# ProProject_PetCareSTM32_MiniSTM32_2024-0.net
KiCad netlist of a schematic drawn in EasyEDA Pro
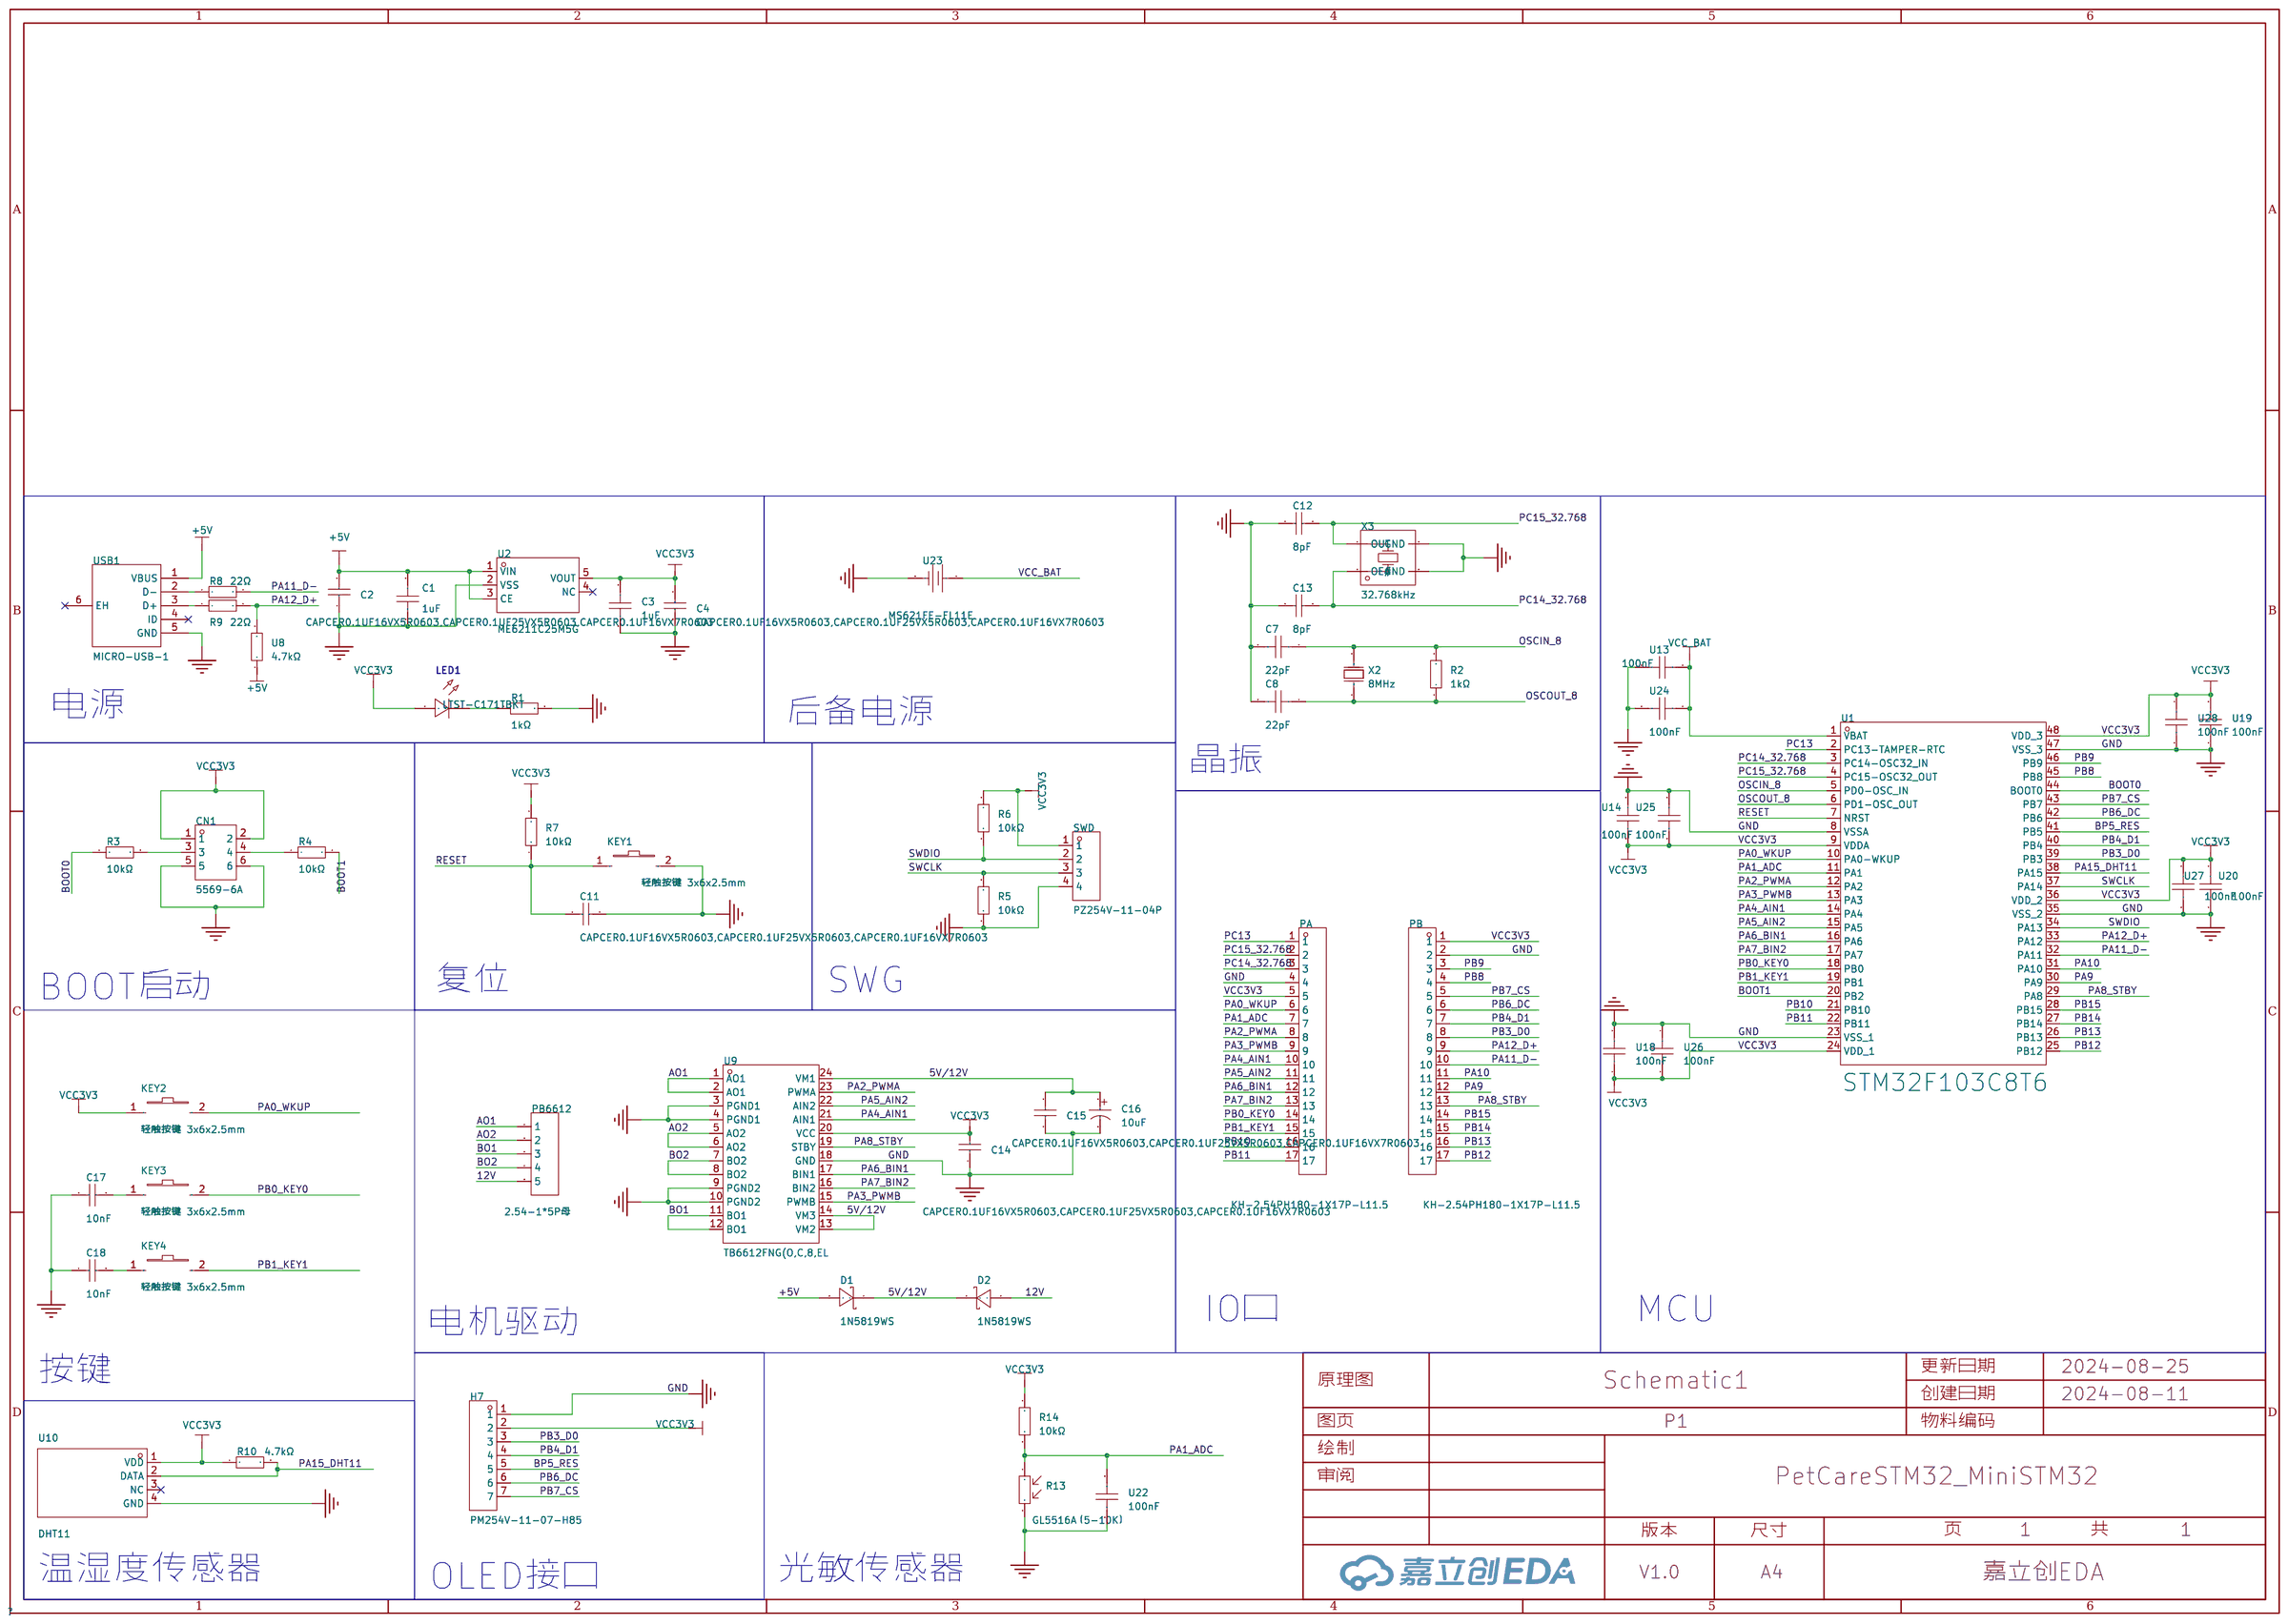
[diagram p0: schematic sheet]

(export (version "E")
  (design (tool "Eeschema 10.0.6"))
  (components
    (comp (ref "C1")
      (value "1uF")
      (footprint "easyedapro:C0603")
      (description "容值:1uF;精度:±10%;额定电压:50V;材质(温度系数):X5R;")
      (fields
        (field (name "Manufacturer Part") "CL10A105KB8NNNC")
        (field (name "Manufacturer") "SAMSUNG(三星)")
      )
      (libsource (lib "easyedapro") (part "CL10A105KB8NNNC"))
    )
    (comp (ref "C2")
      (value "CAPCER0.1UF16VX5R0603,CAPCER0.1UF25VX5R0603,CAPCER0.1UF16VX7R0603")
      (footprint "easyedapro:C0603")
      (libsource (lib "easyedapro") (part "CAPCER0.1UF16VX5R0603,CAPCER0.1UF25VX5R0603,CAPCER0.1UF16VX7R0603"))
    )
    (comp (ref "C3")
      (value "1uF")
      (footprint "easyedapro:C0603")
      (description "容值:1uF;精度:±10%;额定电压:50V;材质(温度系数):X5R;")
      (fields
        (field (name "Manufacturer Part") "CL10A105KB8NNNC")
        (field (name "Manufacturer") "SAMSUNG(三星)")
      )
      (libsource (lib "easyedapro") (part "CL10A105KB8NNNC"))
    )
    (comp (ref "C4")
      (value "CAPCER0.1UF16VX5R0603,CAPCER0.1UF25VX5R0603,CAPCER0.1UF16VX7R0603")
      (footprint "easyedapro:C0603")
      (libsource (lib "easyedapro") (part "CAPCER0.1UF16VX5R0603,CAPCER0.1UF25VX5R0603,CAPCER0.1UF16VX7R0603"))
    )
    (comp (ref "C7")
      (value "22pF")
      (footprint "easyedapro:C0603")
      (description "容值:22pF;精度:±5%;额定电压:50V;材质(温度系数):C0G;")
      (fields
        (field (name "Manufacturer Part") "CL10C220JB81PNC")
        (field (name "Manufacturer") "SAMSUNG(三星)")
      )
      (libsource (lib "easyedapro") (part "CL10C220JB81PNC"))
    )
    (comp (ref "C8")
      (value "22pF")
      (footprint "easyedapro:C0603")
      (description "容值:22pF;精度:±5%;额定电压:50V;材质(温度系数):C0G;")
      (fields
        (field (name "Manufacturer Part") "CL10C220JB81PNC")
        (field (name "Manufacturer") "SAMSUNG(三星)")
      )
      (libsource (lib "easyedapro") (part "CL10C220JB81PNC"))
    )
    (comp (ref "C11")
      (value "CAPCER0.1UF16VX5R0603,CAPCER0.1UF25VX5R0603,CAPCER0.1UF16VX7R0603")
      (footprint "easyedapro:C0603")
      (libsource (lib "easyedapro") (part "CAPCER0.1UF16VX5R0603,CAPCER0.1UF25VX5R0603,CAPCER0.1UF16VX7R0603"))
    )
    (comp (ref "C12")
      (value "8pF")
      (footprint "easyedapro:C0603")
      (description "容值:8pF;额定电压:50V;材质(温度系数):C0G;")
      (fields (field (name "Manufacturer Part") "0603CG8R0C500NT") (field (name "Manufacturer") "FH(风华)"))
      (libsource (lib "easyedapro") (part "0603CG8R0C500NT_C36508"))
    )
    (comp (ref "C13")
      (value "8pF")
      (footprint "easyedapro:C0603")
      (description "容值:8pF;额定电压:50V;材质(温度系数):C0G;")
      (fields (field (name "Manufacturer Part") "0603CG8R0C500NT") (field (name "Manufacturer") "FH(风华)"))
      (libsource (lib "easyedapro") (part "0603CG8R0C500NT_C36508"))
    )
    (comp (ref "C14")
      (value "CAPCER0.1UF16VX5R0603,CAPCER0.1UF25VX5R0603,CAPCER0.1UF16VX7R0603")
      (footprint "easyedapro:C0603")
      (libsource (lib "easyedapro") (part "CAPCER0.1UF16VX5R0603,CAPCER0.1UF25VX5R0603,CAPCER0.1UF16VX7R0603"))
    )
    (comp (ref "C15")
      (value "CAPCER0.1UF16VX5R0603,CAPCER0.1UF25VX5R0603,CAPCER0.1UF16VX7R0603")
      (footprint "easyedapro:C0603")
      (libsource (lib "easyedapro") (part "CAPCER0.1UF16VX5R0603,CAPCER0.1UF25VX5R0603,CAPCER0.1UF16VX7R0603"))
    )
    (comp (ref "C16")
      (value "10uF")
      (footprint "easyedapro:CAP-TH_BD5.0-P2.00-D0.8-FD")
      (description "容值:10uF;精度:±20%;额定电压:25V;")
      (fields (field (name "Manufacturer Part") "KF100M025C110A") (field (name "Manufacturer") "CapXon(丰宾)"))
      (libsource (lib "easyedapro") (part "KF100M025C110A"))
    )
    (comp (ref "C17")
      (value "10nF")
      (footprint "easyedapro:C0603")
      (description "容值:10nF;精度:±10%;额定电压:50V;材质(温度系数):X7R;")
      (fields
        (field (name "Manufacturer Part") "CC0603KRX7R9BB103")
        (field (name "Manufacturer") "YAGEO(国巨)")
      )
      (libsource (lib "easyedapro") (part "CC0603KRX7R9BB103"))
    )
    (comp (ref "C18")
      (value "10nF")
      (footprint "easyedapro:C0603")
      (description "容值:10nF;精度:±10%;额定电压:50V;材质(温度系数):X7R;")
      (fields
        (field (name "Manufacturer Part") "CC0603KRX7R9BB103")
        (field (name "Manufacturer") "YAGEO(国巨)")
      )
      (libsource (lib "easyedapro") (part "CC0603KRX7R9BB103"))
    )
    (comp (ref "CN1")
      (value "5569-6A")
      (footprint "easyedapro:CONN-TH_6P-P4.20_5569-6A-1")
      (libsource (lib "easyedapro") (part "5569-6A"))
    )
    (comp (ref "D1")
      (value "1N5819WS")
      (footprint "easyedapro:SOD-323_L1.8-W1.3-LS2.5-RD")
      (description "正向压降(Vf):600mV@1A;直流反向耐压(Vr):40V;平均整流电流(Io):1A;")
      (fields (field (name "Manufacturer") "Hottech(合科泰)"))
      (libsource (lib "easyedapro") (part "1N5819WS"))
    )
    (comp (ref "D2")
      (value "1N5819WS")
      (footprint "easyedapro:SOD-323_L1.8-W1.3-LS2.5-RD")
      (description "正向压降(Vf):600mV@1A;直流反向耐压(Vr):40V;平均整流电流(Io):1A;")
      (fields (field (name "Manufacturer") "Hottech(合科泰)"))
      (libsource (lib "easyedapro") (part "1N5819WS"))
    )
    (comp (ref "H7")
      (value "PM254V-11-07-H85")
      (footprint "easyedapro:HDR-TH_7P-P2.54-V-F")
      (fields (field (name "Manufacturer") "XFCN(兴飞)"))
      (libsource (lib "easyedapro") (part "PM254V-11-07-H85"))
    )
    (comp (ref "KEY1")
      (value "轻触按键 3x6x2.5mm")
      (footprint "easyedapro:SW-SMD_L6.0-W3.6-LS8.0")
      (libsource (lib "easyedapro") (part "3x6x2.5mm"))
    )
    (comp (ref "KEY2")
      (value "轻触按键 3x6x2.5mm")
      (footprint "easyedapro:SW-SMD_L6.0-W3.6-LS8.0")
      (libsource (lib "easyedapro") (part "3x6x2.5mm"))
    )
    (comp (ref "KEY3")
      (value "轻触按键 3x6x2.5mm")
      (footprint "easyedapro:SW-SMD_L6.0-W3.6-LS8.0")
      (libsource (lib "easyedapro") (part "3x6x2.5mm"))
    )
    (comp (ref "KEY4")
      (value "轻触按键 3x6x2.5mm")
      (footprint "easyedapro:SW-SMD_L6.0-W3.6-LS8.0")
      (libsource (lib "easyedapro") (part "3x6x2.5mm"))
    )
    (comp (ref "LED1")
      (value "LTST-C171TBKT")
      (footprint "easyedapro:LED_0805")
      (fields (field (name "Manufacturer") "LITEON(光宝)"))
      (libsource (lib "easyedapro") (part "LED_B"))
    )
    (comp (ref "PA")
      (value "KH-2.54PH180-1X17P-L11.5")
      (footprint "easyedapro:HDR-TH_17P-P2.54-V-M")
      (fields (field (name "Manufacturer") "kinghelm(金航标)"))
      (libsource (lib "easyedapro") (part "KH-2.54PH180-1X17P-L11.5"))
    )
    (comp (ref "PB")
      (value "KH-2.54PH180-1X17P-L11.5")
      (footprint "easyedapro:HDR-TH_17P-P2.54-V-M")
      (fields (field (name "Manufacturer") "kinghelm(金航标)"))
      (libsource (lib "easyedapro") (part "KH-2.54PH180-1X17P-L11.5"))
    )
    (comp (ref "PB6612")
      (value "2.54-1*5P母")
      (footprint "easyedapro:HDR-TH_5P-P2.54-V-F")
      (description "插孔结构:1x5P;间距:2.54mm;行距:-;安装类型:直插;排数:单排;总孔位数:5P;塑高:-;触头材质:-;触头镀层:-;")
      (fields (field (name "Manufacturer") "BOOMELE(博穆精密)"))
      (libsource (lib "easyedapro") (part "Header-Female-2.54_1x5"))
    )
    (comp (ref "R1")
      (value "1kΩ")
      (footprint "easyedapro:R0603")
      (description "电阻类型:厚膜电阻;阻值:1kΩ;精度:±1%;功率:100mW;最大工作电压:75V;温度系数:±100ppm/°C;")
      (fields (field (name "Manufacturer Part") "RC0603FR-071KL") (field (name "Manufacturer") "YAGEO(国巨)"))
      (libsource (lib "easyedapro") (part "RC0603FR-071KL"))
    )
    (comp (ref "R2")
      (value "1kΩ")
      (footprint "easyedapro:R0603")
      (description "电阻类型:厚膜电阻;阻值:1kΩ;精度:±0.5%;功率:100mW;最大工作电压:75V;温度系数:±100ppm/°C;")
      (fields
        (field (name "Manufacturer Part") "0603WAD1001T5E")
        (field (name "Manufacturer") "UNI-ROYAL(厚声)")
      )
      (libsource (lib "easyedapro") (part "0603WAD1001T5E"))
    )
    (comp (ref "R3")
      (value "10kΩ")
      (footprint "easyedapro:R0603")
      (description "电阻类型:厚膜电阻;阻值:10kΩ;精度:±1%;功率:100mW;最大工作电压:75V;温度系数:±100ppm/°C;")
      (fields
        (field (name "Manufacturer Part") "0603WAF1002T5E")
        (field (name "Manufacturer") "UNI-ROYAL(厚声)")
      )
      (libsource (lib "easyedapro") (part "0603WAF1002T5E"))
    )
    (comp (ref "R4")
      (value "10kΩ")
      (footprint "easyedapro:R0603")
      (description "电阻类型:厚膜电阻;阻值:10kΩ;精度:±1%;功率:100mW;最大工作电压:75V;温度系数:±100ppm/°C;")
      (fields
        (field (name "Manufacturer Part") "0603WAF1002T5E")
        (field (name "Manufacturer") "UNI-ROYAL(厚声)")
      )
      (libsource (lib "easyedapro") (part "0603WAF1002T5E"))
    )
    (comp (ref "R5")
      (value "10kΩ")
      (footprint "easyedapro:R0603")
      (description "电阻类型:厚膜电阻;阻值:10kΩ;精度:±1%;功率:100mW;最大工作电压:75V;温度系数:±100ppm/°C;")
      (fields
        (field (name "Manufacturer Part") "0603WAF1002T5E")
        (field (name "Manufacturer") "UNI-ROYAL(厚声)")
      )
      (libsource (lib "easyedapro") (part "0603WAF1002T5E"))
    )
    (comp (ref "R6")
      (value "10kΩ")
      (footprint "easyedapro:R0603")
      (description "电阻类型:厚膜电阻;阻值:10kΩ;精度:±1%;功率:100mW;最大工作电压:75V;温度系数:±100ppm/°C;")
      (fields
        (field (name "Manufacturer Part") "0603WAF1002T5E")
        (field (name "Manufacturer") "UNI-ROYAL(厚声)")
      )
      (libsource (lib "easyedapro") (part "0603WAF1002T5E"))
    )
    (comp (ref "R7")
      (value "10kΩ")
      (footprint "easyedapro:R0603")
      (description "电阻类型:厚膜电阻;阻值:10kΩ;精度:±1%;功率:100mW;最大工作电压:75V;温度系数:±100ppm/°C;")
      (fields
        (field (name "Manufacturer Part") "0603WAF1002T5E")
        (field (name "Manufacturer") "UNI-ROYAL(厚声)")
      )
      (libsource (lib "easyedapro") (part "0603WAF1002T5E"))
    )
    (comp (ref "R8")
      (value "22Ω")
      (footprint "easyedapro:R0805")
      (description "电阻类型:薄膜电阻;阻值:22Ω;精度:±1%;功率:250mW;最大工作电压:150V;温度系数:±25ppm/°C;")
      (fields
        (field (name "Manufacturer Part") "TC0525F220JT5E")
        (field (name "Manufacturer") "UNI-ROYAL(厚声)")
      )
      (libsource (lib "easyedapro") (part "TC0525F220JT5E"))
    )
    (comp (ref "R9")
      (value "22Ω")
      (footprint "easyedapro:R0805")
      (description "电阻类型:薄膜电阻;阻值:22Ω;精度:±1%;功率:250mW;最大工作电压:150V;温度系数:±25ppm/°C;")
      (fields
        (field (name "Manufacturer Part") "TC0525F220JT5E")
        (field (name "Manufacturer") "UNI-ROYAL(厚声)")
      )
      (libsource (lib "easyedapro") (part "TC0525F220JT5E"))
    )
    (comp (ref "R10")
      (value "4.7kΩ")
      (footprint "easyedapro:R1206")
      (description "电阻类型:厚膜电阻;阻值:4.7kΩ;精度:±1%;功率:250mW;最大工作电压:200V;温度系数:±100ppm/°C;")
      (fields
        (field (name "Manufacturer Part") "1206W4F4701T5E")
        (field (name "Manufacturer") "UNI-ROYAL(厚声)")
      )
      (libsource (lib "easyedapro") (part "1206W4F4701T5E"))
    )
    (comp (ref "R13")
      (value "GL5516A（5-10K）")
      (footprint "easyedapro:RES-TH_L5.1-W4.3-P3.40_GL55")
      (description "暗电阻:200kΩ;亮电阻 @ 10Lux:5kΩ~10kΩ;光谱峰值(波长):540nm;")
      (fields (field (name "Manufacturer") "JCHL(晶创和立)"))
      (libsource (lib "easyedapro") (part "GL5516A(5-10K)"))
    )
    (comp (ref "R14")
      (value "10kΩ")
      (footprint "easyedapro:R0603")
      (description "电阻类型:厚膜电阻;阻值:10kΩ;精度:±1%;功率:100mW;最大工作电压:75V;温度系数:±100ppm/°C;")
      (fields
        (field (name "Manufacturer Part") "0603WAF1002T5E")
        (field (name "Manufacturer") "UNI-ROYAL(厚声)")
      )
      (libsource (lib "easyedapro") (part "0603WAF1002T5E"))
    )
    (comp (ref "SWD")
      (value "PZ254V-11-04P")
      (footprint "easyedapro:HDR-TH_4P-P2.54-V-M")
      (fields (field (name "Manufacturer") "XFCN(兴飞)"))
      (libsource (lib "easyedapro") (part "PZ254V-11-04P_C2691448"))
    )
    (comp (ref "U1")
      (value "STM32F103C8T6")
      (footprint "easyedapro:LQFP-48_L7.0-W7.0-P0.50-LS9.0-BL")
      (description "CPU内核:ARM-M3;程序存储容量:64KB;RAM总容量:20KB;GPIO端口数量:37;工作电压范围:2V~3.6V;CPU最大主频:72MHz;程序存储器类型:FLASH;")
      (fields (field (name "Manufacturer") "ST(意法半导体)"))
      (libsource (lib "easyedapro") (part "STM32F103C8T6"))
    )
    (comp (ref "U2")
      (value "ME6211C25M5G")
      (footprint "easyedapro:SOT-23-5_L2.9-W1.7-P0.95-LS2.8-BL")
      (fields (field (name "Manufacturer") "MICRONE(南京微盟)"))
      (libsource (lib "easyedapro") (part "ME6211C25M5G"))
    )
    (comp (ref "U8")
      (value "4.7kΩ")
      (footprint "easyedapro:R0603")
      (description "电阻类型:薄膜电阻;阻值:4.7kΩ;精度:±1%;功率:100mW;最大工作电压:75V;温度系数:±50ppm/°C;")
      (fields (field (name "Manufacturer Part") "AR03FTDX4701A") (field (name "Manufacturer") "Viking(光颉)"))
      (libsource (lib "easyedapro") (part "AR03FTDX4701A"))
    )
    (comp (ref "U9")
      (value "TB6612FNG(O,C,8,EL")
      (footprint "easyedapro:SSOP-24_L8.4-W5.8-P0.65-LS7.8-BL")
      (description "双直流电机驱动器集成电路")
      (fields (field (name "Manufacturer") "TOSHIBA(东芝)"))
      (libsource (lib "easyedapro") (part "TB6612FNG(O,C,8,EL"))
    )
    (comp (ref "U10")
      (value "DHT11")
      (footprint "easyedapro:SENSOR-TH_DHT11")
      (description "新款电容式数字温湿度传感器,老款已停产16.1x12.6x5.8mm")
      (fields (field (name "Manufacturer") "广州奥松"))
      (libsource (lib "easyedapro") (part "DHT11"))
    )
    (comp (ref "U13")
      (value "100nF")
      (footprint "easyedapro:C0603")
      (description "容值:100nF;精度:±10%;额定电压:50V;材质(温度系数):X7R;")
      (fields
        (field (name "Manufacturer Part") "CGA0603X7R104K500JT")
        (field (name "Manufacturer") "HRE(芯声)")
      )
      (libsource (lib "easyedapro") (part "CGA0603X7R104K500JT"))
    )
    (comp (ref "U14")
      (value "100nF")
      (footprint "easyedapro:C0603")
      (description "容值:100nF;精度:±10%;额定电压:50V;材质(温度系数):X7R;")
      (fields
        (field (name "Manufacturer Part") "CGA0603X7R104K500JT")
        (field (name "Manufacturer") "HRE(芯声)")
      )
      (libsource (lib "easyedapro") (part "CGA0603X7R104K500JT"))
    )
    (comp (ref "U18")
      (value "100nF")
      (footprint "easyedapro:C0603")
      (description "容值:100nF;精度:±10%;额定电压:50V;材质(温度系数):X7R;")
      (fields
        (field (name "Manufacturer Part") "CGA0603X7R104K500JT")
        (field (name "Manufacturer") "HRE(芯声)")
      )
      (libsource (lib "easyedapro") (part "CGA0603X7R104K500JT"))
    )
    (comp (ref "U19")
      (value "100nF")
      (footprint "easyedapro:C0603")
      (description "容值:100nF;精度:±10%;额定电压:50V;材质(温度系数):X7R;")
      (fields
        (field (name "Manufacturer Part") "CGA0603X7R104K500JT")
        (field (name "Manufacturer") "HRE(芯声)")
      )
      (libsource (lib "easyedapro") (part "CGA0603X7R104K500JT"))
    )
    (comp (ref "U20")
      (value "100nF")
      (footprint "easyedapro:C0603")
      (description "容值:100nF;精度:±10%;额定电压:50V;材质(温度系数):X7R;")
      (fields
        (field (name "Manufacturer Part") "CGA0603X7R104K500JT")
        (field (name "Manufacturer") "HRE(芯声)")
      )
      (libsource (lib "easyedapro") (part "CGA0603X7R104K500JT"))
    )
    (comp (ref "U22")
      (value "100nF")
      (footprint "easyedapro:C0603")
      (description "容值:100nF;精度:±10%;额定电压:50V;材质(温度系数):X7R;")
      (fields
        (field (name "Manufacturer Part") "CGA0603X7R104K500JT")
        (field (name "Manufacturer") "HRE(芯声)")
      )
      (libsource (lib "easyedapro") (part "CGA0603X7R104K500JT"))
    )
    (comp (ref "U23")
      (value "MS621FE-FL11E")
      (footprint "easyedapro:BAT-SMD_FL11E")
      (description "FL11E 3.3V可充电纽扣电池 5.5mAH")
      (fields (field (name "Manufacturer") "Seiko(精工)"))
      (libsource (lib "easyedapro") (part "MS621FE-FL11E"))
    )
    (comp (ref "U24")
      (value "100nF")
      (footprint "easyedapro:C0603")
      (description "容值:100nF;精度:±10%;额定电压:50V;材质(温度系数):X7R;")
      (fields
        (field (name "Manufacturer Part") "CGA0603X7R104K500JT")
        (field (name "Manufacturer") "HRE(芯声)")
      )
      (libsource (lib "easyedapro") (part "CGA0603X7R104K500JT"))
    )
    (comp (ref "U25")
      (value "100nF")
      (footprint "easyedapro:C0603")
      (description "容值:100nF;精度:±10%;额定电压:50V;材质(温度系数):X7R;")
      (fields
        (field (name "Manufacturer Part") "CGA0603X7R104K500JT")
        (field (name "Manufacturer") "HRE(芯声)")
      )
      (libsource (lib "easyedapro") (part "CGA0603X7R104K500JT"))
    )
    (comp (ref "U26")
      (value "100nF")
      (footprint "easyedapro:C0603")
      (description "容值:100nF;精度:±10%;额定电压:50V;材质(温度系数):X7R;")
      (fields
        (field (name "Manufacturer Part") "CGA0603X7R104K500JT")
        (field (name "Manufacturer") "HRE(芯声)")
      )
      (libsource (lib "easyedapro") (part "CGA0603X7R104K500JT"))
    )
    (comp (ref "U27")
      (value "100nF")
      (footprint "easyedapro:C0603")
      (description "容值:100nF;精度:±10%;额定电压:50V;材质(温度系数):X7R;")
      (fields
        (field (name "Manufacturer Part") "CGA0603X7R104K500JT")
        (field (name "Manufacturer") "HRE(芯声)")
      )
      (libsource (lib "easyedapro") (part "CGA0603X7R104K500JT"))
    )
    (comp (ref "U28")
      (value "100nF")
      (footprint "easyedapro:C0603")
      (description "容值:100nF;精度:±10%;额定电压:50V;材质(温度系数):X7R;")
      (fields
        (field (name "Manufacturer Part") "CGA0603X7R104K500JT")
        (field (name "Manufacturer") "HRE(芯声)")
      )
      (libsource (lib "easyedapro") (part "CGA0603X7R104K500JT"))
    )
    (comp (ref "USB1")
      (value "MICRO-USB-1")
      (footprint "easyedapro:MICRO-USB-SMD_C9900008946")
      (libsource (lib "easyedapro") (part "MICRO-USB-1"))
    )
    (comp (ref "X2")
      (value "8MHz")
      (footprint "easyedapro:OSC-SMD_L5.0-W3.2")
      (description "晶振类型:贴片晶振;频率:8MHz;常温频差:±20ppm;外接负载电容:18pF;频率稳定度(全温):±30ppm;")
      (fields
        (field (name "Manufacturer Part") "ABM3-8.000MHZ-D2Y-T")
        (field (name "Manufacturer") "ABRACON")
      )
      (libsource (lib "easyedapro") (part "ABM3-8.000MHZ-D2Y-T"))
    )
    (comp (ref "X3")
      (value "32.768kHz")
      (footprint "easyedapro:CRYSTAL-SMD_4P-L8.0-W3.8-BL")
      (description "晶振类型:-;频率:32.768kHz;常温频差:±20ppm;外接负载电容:12.5pF;频率稳定度(全温):-;")
      (fields (field (name "Manufacturer Part") "ABS25-32.768KHZ-T") (field (name "Manufacturer") "ABRACON"))
      (libsource (lib "easyedapro") (part "ABS25-32.768KHZ-T"))
    )
  )
  (nets
    (net (code "1") (name "+5V") (class "Default")
      (node (ref "C1") (pin "2") (pinfunction "2_2") (pintype "unspecified"))
      (node (ref "C2") (pin "2") (pinfunction "2_2") (pintype "input"))
      (node (ref "D1") (pin "2") (pinfunction "A_2") (pintype "unspecified"))
      (node (ref "U2") (pin "1") (pinfunction "VIN_1") (pintype "unspecified"))
      (node (ref "U2") (pin "3") (pinfunction "CE_3") (pintype "unspecified"))
      (node (ref "U8") (pin "1") (pinfunction "1_1") (pintype "unspecified"))
      (node (ref "USB1") (pin "1") (pinfunction "VBUS_1") (pintype "input"))
    )
    (net (code "2") (name "/5V{slash}12V") (class "Default")
      (node (ref "C15") (pin "2") (pinfunction "2_2") (pintype "input"))
      (node (ref "C16") (pin "1") (pinfunction "1_1") (pintype "input"))
      (node (ref "D1") (pin "1") (pinfunction "K_1") (pintype "unspecified"))
      (node (ref "D2") (pin "1") (pinfunction "K_1") (pintype "unspecified"))
      (node (ref "U9") (pin "13") (pinfunction "VM2_13") (pintype "unspecified"))
      (node (ref "U9") (pin "14") (pinfunction "VM3_14") (pintype "unspecified"))
      (node (ref "U9") (pin "24") (pinfunction "VM1_24") (pintype "unspecified"))
    )
    (net (code "3") (name "/12V") (class "Default")
      (node (ref "D2") (pin "2") (pinfunction "A_2") (pintype "unspecified"))
      (node (ref "PB6612") (pin "5") (pinfunction "5_5") (pintype "input"))
    )
    (net (code "4") (name "/AO1") (class "Default")
      (node (ref "PB6612") (pin "1") (pinfunction "1_1") (pintype "input"))
      (node (ref "U9") (pin "1") (pinfunction "AO1_1") (pintype "unspecified"))
      (node (ref "U9") (pin "2") (pinfunction "AO1_2") (pintype "unspecified"))
    )
    (net (code "5") (name "/AO2") (class "Default")
      (node (ref "PB6612") (pin "2") (pinfunction "2_2") (pintype "input"))
      (node (ref "U9") (pin "5") (pinfunction "AO2_5") (pintype "unspecified"))
      (node (ref "U9") (pin "6") (pinfunction "AO2_6") (pintype "unspecified"))
    )
    (net (code "6") (name "/BO1") (class "Default")
      (node (ref "PB6612") (pin "3") (pinfunction "3_3") (pintype "input"))
      (node (ref "U9") (pin "11") (pinfunction "BO1_11") (pintype "unspecified"))
      (node (ref "U9") (pin "12") (pinfunction "BO1_12") (pintype "unspecified"))
    )
    (net (code "7") (name "/BO2") (class "Default")
      (node (ref "PB6612") (pin "4") (pinfunction "4_4") (pintype "input"))
      (node (ref "U9") (pin "7") (pinfunction "BO2_7") (pintype "unspecified"))
      (node (ref "U9") (pin "8") (pinfunction "BO2_8") (pintype "unspecified"))
    )
    (net (code "8") (name "/BOOT0") (class "Default")
      (node (ref "R3") (pin "1") (pinfunction "1_1") (pintype "input"))
      (node (ref "U1") (pin "44") (pinfunction "BOOT0_44") (pintype "unspecified"))
    )
    (net (code "9") (name "/BOOT1") (class "Default")
      (node (ref "R4") (pin "2") (pinfunction "2_2") (pintype "input"))
      (node (ref "U1") (pin "20") (pinfunction "PB2_20") (pintype "unspecified"))
    )
    (net (code "10") (name "/BP5_RES") (class "Default")
      (node (ref "H7") (pin "5") (pinfunction "5_5") (pintype "unspecified"))
      (node (ref "U1") (pin "41") (pinfunction "PB5_41") (pintype "unspecified"))
    )
    (net (code "11") (name "/OSCIN_8") (class "Default")
      (node (ref "C7") (pin "1") (pinfunction "1_1") (pintype "unspecified"))
      (node (ref "R2") (pin "2") (pinfunction "2_2") (pintype "input"))
      (node (ref "U1") (pin "5") (pinfunction "PD0-OSC_IN_5") (pintype "unspecified"))
      (node (ref "X2") (pin "2") (pinfunction "OSC2_2") (pintype "input"))
    )
    (net (code "12") (name "/OSCOUT_8") (class "Default")
      (node (ref "C8") (pin "1") (pinfunction "1_1") (pintype "unspecified"))
      (node (ref "R2") (pin "1") (pinfunction "1_1") (pintype "input"))
      (node (ref "U1") (pin "6") (pinfunction "PD1-OSC_OUT_6") (pintype "unspecified"))
      (node (ref "X2") (pin "1") (pinfunction "OSC1_1") (pintype "input"))
    )
    (net (code "13") (name "/PA0_WKUP") (class "Default")
      (node (ref "KEY2") (pin "2") (pinfunction "2_2") (pintype "input"))
      (node (ref "PA") (pin "6") (pinfunction "6_6") (pintype "unspecified"))
      (node (ref "U1") (pin "10") (pinfunction "PA0-WKUP_10") (pintype "unspecified"))
    )
    (net (code "14") (name "/PA1_ADC") (class "Default")
      (node (ref "PA") (pin "7") (pinfunction "7_7") (pintype "unspecified"))
      (node (ref "R13") (pin "1") (pinfunction "1_1") (pintype "input"))
      (node (ref "R14") (pin "1") (pinfunction "1_1") (pintype "input"))
      (node (ref "U1") (pin "11") (pinfunction "PA1_11") (pintype "unspecified"))
      (node (ref "U22") (pin "2") (pinfunction "2_2") (pintype "unspecified"))
    )
    (net (code "15") (name "/PA2_PWMA") (class "Default")
      (node (ref "PA") (pin "8") (pinfunction "8_8") (pintype "unspecified"))
      (node (ref "U1") (pin "12") (pinfunction "PA2_12") (pintype "unspecified"))
      (node (ref "U9") (pin "23") (pinfunction "PWMA_23") (pintype "unspecified"))
    )
    (net (code "16") (name "/PA3_PWMB") (class "Default")
      (node (ref "PA") (pin "9") (pinfunction "9_9") (pintype "unspecified"))
      (node (ref "U1") (pin "13") (pinfunction "PA3_13") (pintype "unspecified"))
      (node (ref "U9") (pin "15") (pinfunction "PWMB_15") (pintype "unspecified"))
    )
    (net (code "17") (name "/PA4_AIN1") (class "Default")
      (node (ref "PA") (pin "10") (pinfunction "10_10") (pintype "unspecified"))
      (node (ref "U1") (pin "14") (pinfunction "PA4_14") (pintype "unspecified"))
      (node (ref "U9") (pin "21") (pinfunction "AIN1_21") (pintype "unspecified"))
    )
    (net (code "18") (name "/PA5_AIN2") (class "Default")
      (node (ref "PA") (pin "11") (pinfunction "11_11") (pintype "unspecified"))
      (node (ref "U1") (pin "15") (pinfunction "PA5_15") (pintype "unspecified"))
      (node (ref "U9") (pin "22") (pinfunction "AIN2_22") (pintype "unspecified"))
    )
    (net (code "19") (name "/PA6_BIN1") (class "Default")
      (node (ref "PA") (pin "12") (pinfunction "12_12") (pintype "unspecified"))
      (node (ref "U1") (pin "16") (pinfunction "PA6_16") (pintype "unspecified"))
      (node (ref "U9") (pin "17") (pinfunction "BIN1_17") (pintype "unspecified"))
    )
    (net (code "20") (name "/PA7_BIN2") (class "Default")
      (node (ref "PA") (pin "13") (pinfunction "13_13") (pintype "unspecified"))
      (node (ref "U1") (pin "17") (pinfunction "PA7_17") (pintype "unspecified"))
      (node (ref "U9") (pin "16") (pinfunction "BIN2_16") (pintype "unspecified"))
    )
    (net (code "21") (name "/PA8_STBY") (class "Default")
      (node (ref "PB") (pin "13") (pinfunction "13_13") (pintype "unspecified"))
      (node (ref "U1") (pin "29") (pinfunction "PA8_29") (pintype "unspecified"))
      (node (ref "U9") (pin "19") (pinfunction "STBY_19") (pintype "unspecified"))
    )
    (net (code "22") (name "/PA9") (class "Default")
      (node (ref "PB") (pin "12") (pinfunction "12_12") (pintype "unspecified"))
      (node (ref "U1") (pin "30") (pinfunction "PA9_30") (pintype "unspecified"))
    )
    (net (code "23") (name "/PA10") (class "Default")
      (node (ref "PB") (pin "11") (pinfunction "11_11") (pintype "unspecified"))
      (node (ref "U1") (pin "31") (pinfunction "PA10_31") (pintype "unspecified"))
    )
    (net (code "24") (name "/PA11_D-") (class "Default")
      (node (ref "PB") (pin "10") (pinfunction "10_10") (pintype "unspecified"))
      (node (ref "R8") (pin "2") (pinfunction "2_2") (pintype "input"))
      (node (ref "U1") (pin "32") (pinfunction "PA11_32") (pintype "unspecified"))
    )
    (net (code "25") (name "/PA12_D+") (class "Default")
      (node (ref "PB") (pin "9") (pinfunction "9_9") (pintype "unspecified"))
      (node (ref "R9") (pin "2") (pinfunction "2_2") (pintype "input"))
      (node (ref "U1") (pin "33") (pinfunction "PA12_33") (pintype "unspecified"))
      (node (ref "U8") (pin "2") (pinfunction "2_2") (pintype "unspecified"))
    )
    (net (code "26") (name "/PA15_DHT11") (class "Default")
      (node (ref "R10") (pin "2") (pinfunction "2_2") (pintype "input"))
      (node (ref "U1") (pin "38") (pinfunction "PA15_38") (pintype "unspecified"))
      (node (ref "U10") (pin "2") (pinfunction "DATA_2") (pintype "unspecified"))
    )
    (net (code "27") (name "/PB0_KEY0") (class "Default")
      (node (ref "KEY3") (pin "2") (pinfunction "2_2") (pintype "input"))
      (node (ref "PA") (pin "14") (pinfunction "14_14") (pintype "unspecified"))
      (node (ref "U1") (pin "18") (pinfunction "PB0_18") (pintype "unspecified"))
    )
    (net (code "28") (name "/PB1_KEY1") (class "Default")
      (node (ref "KEY4") (pin "2") (pinfunction "2_2") (pintype "input"))
      (node (ref "PA") (pin "15") (pinfunction "15_15") (pintype "unspecified"))
      (node (ref "U1") (pin "19") (pinfunction "PB1_19") (pintype "unspecified"))
    )
    (net (code "29") (name "/PB3_D0") (class "Default")
      (node (ref "H7") (pin "3") (pinfunction "3_3") (pintype "unspecified"))
      (node (ref "PB") (pin "8") (pinfunction "8_8") (pintype "unspecified"))
      (node (ref "U1") (pin "39") (pinfunction "PB3_39") (pintype "unspecified"))
    )
    (net (code "30") (name "/PB4_D1") (class "Default")
      (node (ref "H7") (pin "4") (pinfunction "4_4") (pintype "unspecified"))
      (node (ref "PB") (pin "7") (pinfunction "7_7") (pintype "unspecified"))
      (node (ref "U1") (pin "40") (pinfunction "PB4_40") (pintype "unspecified"))
    )
    (net (code "31") (name "/PB6_DC") (class "Default")
      (node (ref "H7") (pin "6") (pinfunction "6_6") (pintype "unspecified"))
      (node (ref "PB") (pin "6") (pinfunction "6_6") (pintype "unspecified"))
      (node (ref "U1") (pin "42") (pinfunction "PB6_42") (pintype "unspecified"))
    )
    (net (code "32") (name "/PB7_CS") (class "Default")
      (node (ref "H7") (pin "7") (pinfunction "7_7") (pintype "unspecified"))
      (node (ref "PB") (pin "5") (pinfunction "5_5") (pintype "unspecified"))
      (node (ref "U1") (pin "43") (pinfunction "PB7_43") (pintype "unspecified"))
    )
    (net (code "33") (name "/PB8") (class "Default")
      (node (ref "PB") (pin "4") (pinfunction "4_4") (pintype "unspecified"))
      (node (ref "U1") (pin "45") (pinfunction "PB8_45") (pintype "unspecified"))
    )
    (net (code "34") (name "/PB9") (class "Default")
      (node (ref "PB") (pin "3") (pinfunction "3_3") (pintype "unspecified"))
      (node (ref "U1") (pin "46") (pinfunction "PB9_46") (pintype "unspecified"))
    )
    (net (code "35") (name "/PB10") (class "Default")
      (node (ref "PA") (pin "16") (pinfunction "16_16") (pintype "unspecified"))
      (node (ref "U1") (pin "21") (pinfunction "PB10_21") (pintype "unspecified"))
    )
    (net (code "36") (name "/PB11") (class "Default")
      (node (ref "PA") (pin "17") (pinfunction "17_17") (pintype "unspecified"))
      (node (ref "U1") (pin "22") (pinfunction "PB11_22") (pintype "unspecified"))
    )
    (net (code "37") (name "/PB12") (class "Default")
      (node (ref "PB") (pin "17") (pinfunction "17_17") (pintype "unspecified"))
      (node (ref "U1") (pin "25") (pinfunction "PB12_25") (pintype "unspecified"))
    )
    (net (code "38") (name "/PB13") (class "Default")
      (node (ref "PB") (pin "16") (pinfunction "16_16") (pintype "unspecified"))
      (node (ref "U1") (pin "26") (pinfunction "PB13_26") (pintype "unspecified"))
    )
    (net (code "39") (name "/PB14") (class "Default")
      (node (ref "PB") (pin "15") (pinfunction "15_15") (pintype "unspecified"))
      (node (ref "U1") (pin "27") (pinfunction "PB14_27") (pintype "unspecified"))
    )
    (net (code "40") (name "/PB15") (class "Default")
      (node (ref "PB") (pin "14") (pinfunction "14_14") (pintype "unspecified"))
      (node (ref "U1") (pin "28") (pinfunction "PB15_28") (pintype "unspecified"))
    )
    (net (code "41") (name "/PC13") (class "Default")
      (node (ref "PA") (pin "1") (pinfunction "1_1") (pintype "unspecified"))
      (node (ref "U1") (pin "2") (pinfunction "PC13-TAMPER-RTC_2") (pintype "unspecified"))
    )
    (net (code "42") (name "/PC14_32.768") (class "Default")
      (node (ref "C13") (pin "2") (pinfunction "2_2") (pintype "input"))
      (node (ref "PA") (pin "3") (pinfunction "3_3") (pintype "unspecified"))
      (node (ref "U1") (pin "3") (pinfunction "PC14-OSC32_IN_3") (pintype "unspecified"))
      (node (ref "X3") (pin "1") (pinfunction "OE#_1") (pintype "input"))
    )
    (net (code "43") (name "/PC15_32.768") (class "Default")
      (node (ref "C12") (pin "2") (pinfunction "2_2") (pintype "input"))
      (node (ref "PA") (pin "2") (pinfunction "2_2") (pintype "unspecified"))
      (node (ref "U1") (pin "4") (pinfunction "PC15-OSC32_OUT_4") (pintype "unspecified"))
      (node (ref "X3") (pin "4") (pinfunction "OUT_4") (pintype "input"))
    )
    (net (code "44") (name "/RESET") (class "Default")
      (node (ref "C11") (pin "1") (pinfunction "1_1") (pintype "input"))
      (node (ref "KEY1") (pin "1") (pinfunction "1_1") (pintype "input"))
      (node (ref "R7") (pin "1") (pinfunction "1_1") (pintype "input"))
      (node (ref "U1") (pin "7") (pinfunction "NRST_7") (pintype "unspecified"))
    )
    (net (code "45") (name "/SWCLK") (class "Default")
      (node (ref "R5") (pin "2") (pinfunction "2_2") (pintype "input"))
      (node (ref "SWD") (pin "3") (pinfunction "3_3") (pintype "unspecified"))
      (node (ref "U1") (pin "37") (pinfunction "PA14_37") (pintype "unspecified"))
    )
    (net (code "46") (name "/SWDIO") (class "Default")
      (node (ref "R6") (pin "1") (pinfunction "1_1") (pintype "input"))
      (node (ref "SWD") (pin "2") (pinfunction "2_2") (pintype "unspecified"))
      (node (ref "U1") (pin "34") (pinfunction "PA13_34") (pintype "unspecified"))
    )
    (net (code "47") (name "GND") (class "Default")
      (node (ref "C1") (pin "1") (pinfunction "1_1") (pintype "unspecified"))
      (node (ref "C11") (pin "2") (pinfunction "2_2") (pintype "input"))
      (node (ref "C12") (pin "1") (pinfunction "1_1") (pintype "input"))
      (node (ref "C13") (pin "1") (pinfunction "1_1") (pintype "input"))
      (node (ref "C14") (pin "1") (pinfunction "1_1") (pintype "input"))
      (node (ref "C15") (pin "1") (pinfunction "1_1") (pintype "input"))
      (node (ref "C16") (pin "2") (pinfunction "2_2") (pintype "input"))
      (node (ref "C17") (pin "2") (pinfunction "2_2") (pintype "input"))
      (node (ref "C18") (pin "1") (pinfunction "1_1") (pintype "input"))
      (node (ref "C2") (pin "1") (pinfunction "1_1") (pintype "input"))
      (node (ref "C3") (pin "1") (pinfunction "1_1") (pintype "unspecified"))
      (node (ref "C4") (pin "1") (pinfunction "1_1") (pintype "input"))
      (node (ref "C7") (pin "2") (pinfunction "2_2") (pintype "unspecified"))
      (node (ref "C8") (pin "2") (pinfunction "2_2") (pintype "unspecified"))
      (node (ref "CN1") (pin "5") (pinfunction "5_5") (pintype "unspecified"))
      (node (ref "CN1") (pin "6") (pinfunction "6_6") (pintype "unspecified"))
      (node (ref "H7") (pin "1") (pinfunction "1_1") (pintype "unspecified"))
      (node (ref "KEY1") (pin "2") (pinfunction "2_2") (pintype "input"))
      (node (ref "PA") (pin "4") (pinfunction "4_4") (pintype "unspecified"))
      (node (ref "PB") (pin "2") (pinfunction "2_2") (pintype "unspecified"))
      (node (ref "R1") (pin "2") (pinfunction "2_2") (pintype "input"))
      (node (ref "R13") (pin "2") (pinfunction "2_2") (pintype "input"))
      (node (ref "R5") (pin "1") (pinfunction "1_1") (pintype "input"))
      (node (ref "SWD") (pin "4") (pinfunction "4_4") (pintype "unspecified"))
      (node (ref "U1") (pin "23") (pinfunction "VSS_1_23") (pintype "unspecified"))
      (node (ref "U1") (pin "35") (pinfunction "VSS_2_35") (pintype "unspecified"))
      (node (ref "U1") (pin "47") (pinfunction "VSS_3_47") (pintype "unspecified"))
      (node (ref "U1") (pin "8") (pinfunction "VSSA_8") (pintype "unspecified"))
      (node (ref "U10") (pin "4") (pinfunction "GND_4") (pintype "unspecified"))
      (node (ref "U13") (pin "2") (pinfunction "2_2") (pintype "unspecified"))
      (node (ref "U14") (pin "2") (pinfunction "2_2") (pintype "unspecified"))
      (node (ref "U18") (pin "2") (pinfunction "2_2") (pintype "unspecified"))
      (node (ref "U19") (pin "1") (pinfunction "1_1") (pintype "unspecified"))
      (node (ref "U2") (pin "2") (pinfunction "VSS_2") (pintype "unspecified"))
      (node (ref "U20") (pin "1") (pinfunction "1_1") (pintype "unspecified"))
      (node (ref "U22") (pin "1") (pinfunction "1_1") (pintype "unspecified"))
      (node (ref "U23") (pin "2") (pinfunction "-_2") (pintype "unspecified"))
      (node (ref "U24") (pin "2") (pinfunction "2_2") (pintype "unspecified"))
      (node (ref "U25") (pin "1") (pinfunction "1_1") (pintype "unspecified"))
      (node (ref "U26") (pin "1") (pinfunction "1_1") (pintype "unspecified"))
      (node (ref "U27") (pin "2") (pinfunction "2_2") (pintype "unspecified"))
      (node (ref "U28") (pin "2") (pinfunction "2_2") (pintype "unspecified"))
      (node (ref "U9") (pin "10") (pinfunction "PGND2_10") (pintype "unspecified"))
      (node (ref "U9") (pin "18") (pinfunction "GND_18") (pintype "unspecified"))
      (node (ref "U9") (pin "3") (pinfunction "PGND1_3") (pintype "unspecified"))
      (node (ref "U9") (pin "4") (pinfunction "PGND1_4") (pintype "unspecified"))
      (node (ref "U9") (pin "9") (pinfunction "PGND2_9") (pintype "unspecified"))
      (node (ref "USB1") (pin "5") (pinfunction "GND_5") (pintype "input"))
      (node (ref "X3") (pin "2") (pinfunction "GND_2") (pintype "input"))
      (node (ref "X3") (pin "3") (pinfunction "GND_3") (pintype "input"))
    )
    (net (code "48") (name "Net-(C17-Pad1)") (class "Default")
      (node (ref "C17") (pin "1") (pinfunction "1_1") (pintype "input"))
      (node (ref "KEY3") (pin "1") (pinfunction "1_1") (pintype "input"))
    )
    (net (code "49") (name "Net-(C18-Pad2)") (class "Default")
      (node (ref "C18") (pin "2") (pinfunction "2_2") (pintype "input"))
      (node (ref "KEY4") (pin "1") (pinfunction "1_1") (pintype "input"))
    )
    (net (code "50") (name "Net-(CN1-Pad3)") (class "Default")
      (node (ref "CN1") (pin "3") (pinfunction "3_3") (pintype "unspecified"))
      (node (ref "R3") (pin "2") (pinfunction "2_2") (pintype "input"))
    )
    (net (code "51") (name "Net-(CN1-Pad4)") (class "Default")
      (node (ref "CN1") (pin "4") (pinfunction "4_4") (pintype "unspecified"))
      (node (ref "R4") (pin "1") (pinfunction "1_1") (pintype "input"))
    )
    (net (code "52") (name "Net-(LED1-C)") (class "Default")
      (node (ref "LED1") (pin "1") (pinfunction "C_1") (pintype "input"))
      (node (ref "R1") (pin "1") (pinfunction "1_1") (pintype "input"))
    )
    (net (code "53") (name "Net-(USB1-D+)") (class "Default")
      (node (ref "R9") (pin "1") (pinfunction "1_1") (pintype "input"))
      (node (ref "USB1") (pin "3") (pinfunction "D+_3") (pintype "input"))
    )
    (net (code "54") (name "Net-(USB1-D-)") (class "Default")
      (node (ref "R8") (pin "1") (pinfunction "1_1") (pintype "input"))
      (node (ref "USB1") (pin "2") (pinfunction "D-_2") (pintype "input"))
    )
    (net (code "55") (name "VCC3V3") (class "Default")
      (node (ref "C14") (pin "2") (pinfunction "2_2") (pintype "input"))
      (node (ref "C3") (pin "2") (pinfunction "2_2") (pintype "unspecified"))
      (node (ref "C4") (pin "2") (pinfunction "2_2") (pintype "input"))
      (node (ref "CN1") (pin "1") (pinfunction "1_1") (pintype "unspecified"))
      (node (ref "CN1") (pin "2") (pinfunction "2_2") (pintype "unspecified"))
      (node (ref "H7") (pin "2") (pinfunction "2_2") (pintype "unspecified"))
      (node (ref "KEY2") (pin "1") (pinfunction "1_1") (pintype "input"))
      (node (ref "LED1") (pin "2") (pinfunction "A_2") (pintype "input"))
      (node (ref "PA") (pin "5") (pinfunction "5_5") (pintype "unspecified"))
      (node (ref "PB") (pin "1") (pinfunction "1_1") (pintype "unspecified"))
      (node (ref "R10") (pin "1") (pinfunction "1_1") (pintype "input"))
      (node (ref "R14") (pin "2") (pinfunction "2_2") (pintype "input"))
      (node (ref "R6") (pin "2") (pinfunction "2_2") (pintype "input"))
      (node (ref "R7") (pin "2") (pinfunction "2_2") (pintype "input"))
      (node (ref "SWD") (pin "1") (pinfunction "1_1") (pintype "unspecified"))
      (node (ref "U1") (pin "24") (pinfunction "VDD_1_24") (pintype "unspecified"))
      (node (ref "U1") (pin "36") (pinfunction "VDD_2_36") (pintype "unspecified"))
      (node (ref "U1") (pin "48") (pinfunction "VDD_3_48") (pintype "unspecified"))
      (node (ref "U1") (pin "9") (pinfunction "VDDA_9") (pintype "unspecified"))
      (node (ref "U10") (pin "1") (pinfunction "VDD_1") (pintype "unspecified"))
      (node (ref "U14") (pin "1") (pinfunction "1_1") (pintype "unspecified"))
      (node (ref "U18") (pin "1") (pinfunction "1_1") (pintype "unspecified"))
      (node (ref "U19") (pin "2") (pinfunction "2_2") (pintype "unspecified"))
      (node (ref "U2") (pin "5") (pinfunction "VOUT_5") (pintype "unspecified"))
      (node (ref "U20") (pin "2") (pinfunction "2_2") (pintype "unspecified"))
      (node (ref "U25") (pin "2") (pinfunction "2_2") (pintype "unspecified"))
      (node (ref "U26") (pin "2") (pinfunction "2_2") (pintype "unspecified"))
      (node (ref "U27") (pin "1") (pinfunction "1_1") (pintype "unspecified"))
      (node (ref "U28") (pin "1") (pinfunction "1_1") (pintype "unspecified"))
      (node (ref "U9") (pin "20") (pinfunction "VCC_20") (pintype "unspecified"))
    )
    (net (code "56") (name "VCC_BAT") (class "Default")
      (node (ref "U1") (pin "1") (pinfunction "VBAT_1") (pintype "unspecified"))
      (node (ref "U13") (pin "1") (pinfunction "1_1") (pintype "unspecified"))
      (node (ref "U23") (pin "1") (pinfunction "+_1") (pintype "unspecified"))
      (node (ref "U24") (pin "1") (pinfunction "1_1") (pintype "unspecified"))
    )
    (net (code "57") (name "unconnected-(U2-NC-Pad4)") (class "Default")
      (node (ref "U2") (pin "4") (pinfunction "NC_4") (pintype "unspecified+no_connect"))
    )
    (net (code "58") (name "unconnected-(U10-NC-Pad3)") (class "Default")
      (node (ref "U10") (pin "3") (pinfunction "NC_3") (pintype "unspecified+no_connect"))
    )
    (net (code "59") (name "unconnected-(USB1-EH-Pad6)") (class "Default")
      (node (ref "USB1") (pin "6") (pinfunction "EH_6") (pintype "input+no_connect"))
    )
    (net (code "60") (name "unconnected-(USB1-ID-Pad4)") (class "Default")
      (node (ref "USB1") (pin "4") (pinfunction "ID_4") (pintype "input+no_connect"))
    )
  )
)
